# Main_Board.net
KiCad netlist of a schematic drawn in Altium Designer
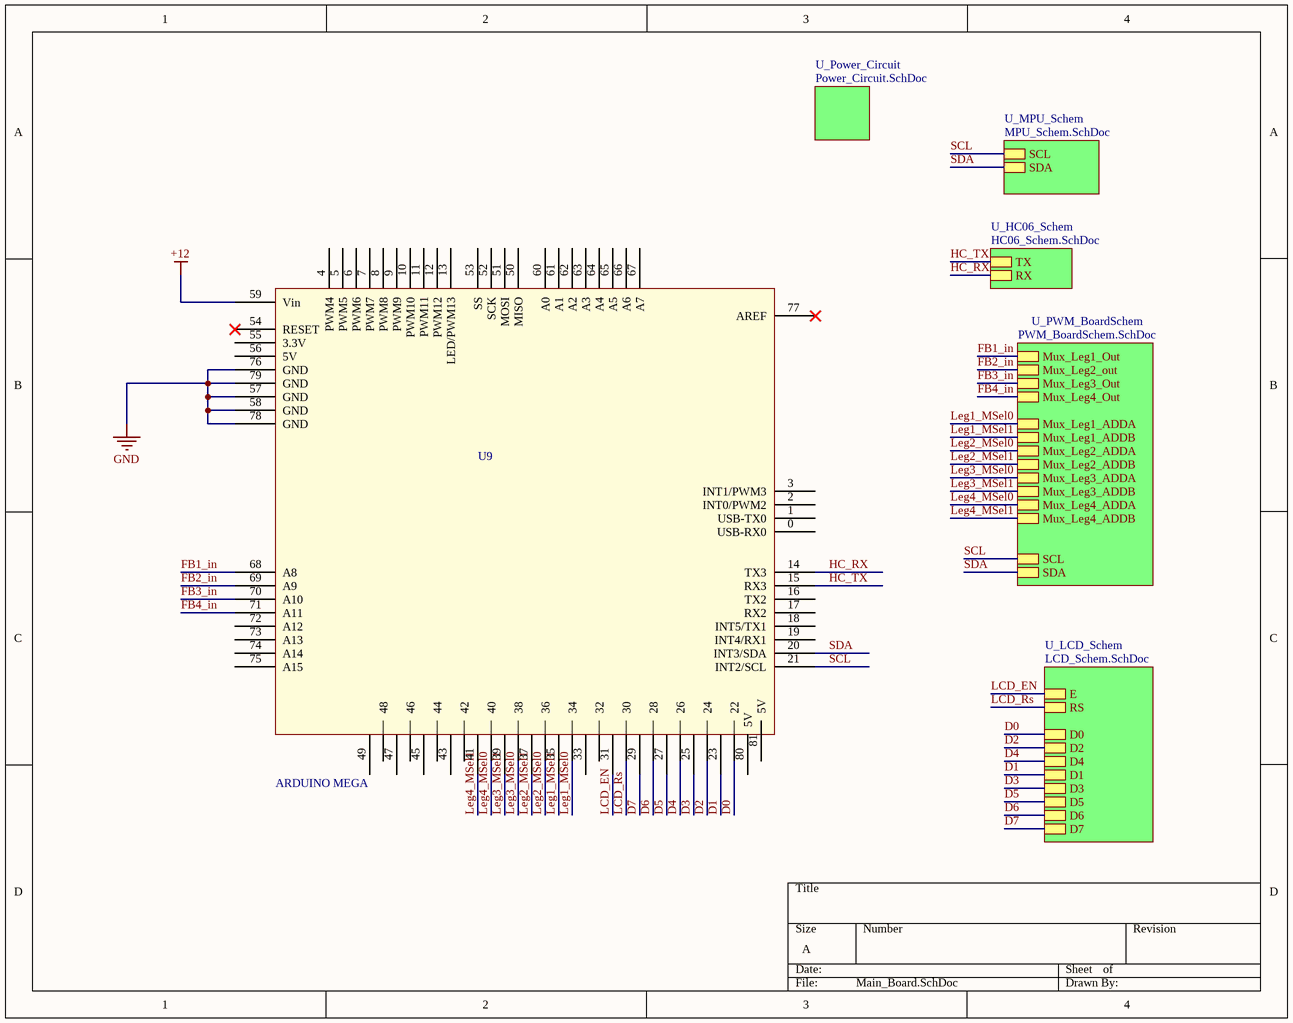
[diagram p0: Main_Board.SchDoc]

(export (version "E")
  (design (tool "Eeschema 10.0.6"))
  (components
    (comp (ref "U9")
      (value "ARDUINO MEGA")
      (footprint "ARDUINO MEGA")
      (libsource (lib "Arduino") (part "ARDUINO MEGA"))
    )
  )
  (nets
    (net (code "1") (name "+12") (class "Default")
      (node (ref "U9") (pin "59") (pinfunction "Vin_59") (pintype "passive"))
    )
    (net (code "2") (name "/D0") (class "Default")
      (node (ref "U9") (pin "22") (pinfunction "22_22") (pintype "passive"))
    )
    (net (code "3") (name "/D1") (class "Default")
      (node (ref "U9") (pin "23") (pinfunction "23_23") (pintype "passive"))
    )
    (net (code "4") (name "/D2") (class "Default")
      (node (ref "U9") (pin "24") (pinfunction "24_24") (pintype "passive"))
    )
    (net (code "5") (name "/D3") (class "Default")
      (node (ref "U9") (pin "25") (pinfunction "25_25") (pintype "passive"))
    )
    (net (code "6") (name "/D4") (class "Default")
      (node (ref "U9") (pin "26") (pinfunction "26_26") (pintype "passive"))
    )
    (net (code "7") (name "/D5") (class "Default")
      (node (ref "U9") (pin "27") (pinfunction "27_27") (pintype "passive"))
    )
    (net (code "8") (name "/D6") (class "Default")
      (node (ref "U9") (pin "28") (pinfunction "28_28") (pintype "passive"))
    )
    (net (code "9") (name "/D7") (class "Default")
      (node (ref "U9") (pin "29") (pinfunction "29_29") (pintype "passive"))
    )
    (net (code "10") (name "/FB1_in") (class "Default")
      (node (ref "U9") (pin "68") (pinfunction "A8_68") (pintype "passive"))
    )
    (net (code "11") (name "/FB2_in") (class "Default")
      (node (ref "U9") (pin "69") (pinfunction "A9_69") (pintype "passive"))
    )
    (net (code "12") (name "/FB3_in") (class "Default")
      (node (ref "U9") (pin "70") (pinfunction "A10_70") (pintype "passive"))
    )
    (net (code "13") (name "/FB4_in") (class "Default")
      (node (ref "U9") (pin "71") (pinfunction "A11_71") (pintype "passive"))
    )
    (net (code "14") (name "/HC_RX") (class "Default")
      (node (ref "U9") (pin "14") (pinfunction "TX3_14") (pintype "passive"))
    )
    (net (code "15") (name "/HC_TX") (class "Default")
      (node (ref "U9") (pin "15") (pinfunction "RX3_15") (pintype "passive"))
    )
    (net (code "16") (name "/LCD_EN") (class "Default")
      (node (ref "U9") (pin "31") (pinfunction "31_31") (pintype "passive"))
    )
    (net (code "17") (name "/LCD_Rs") (class "Default")
      (node (ref "U9") (pin "30") (pinfunction "30_30") (pintype "passive"))
    )
    (net (code "18") (name "/Leg1_MSel0") (class "Default")
      (node (ref "U9") (pin "34") (pinfunction "34_34") (pintype "passive"))
    )
    (net (code "19") (name "/Leg1_MSel1") (class "Default")
      (node (ref "U9") (pin "35") (pinfunction "35_35") (pintype "passive"))
    )
    (net (code "20") (name "/Leg2_MSel0") (class "Default")
      (node (ref "U9") (pin "36") (pinfunction "36_36") (pintype "passive"))
    )
    (net (code "21") (name "/Leg2_MSel1") (class "Default")
      (node (ref "U9") (pin "37") (pinfunction "37_37") (pintype "passive"))
    )
    (net (code "22") (name "/Leg3_MSel0") (class "Default")
      (node (ref "U9") (pin "38") (pinfunction "38_38") (pintype "passive"))
    )
    (net (code "23") (name "/Leg3_MSel1") (class "Default")
      (node (ref "U9") (pin "39") (pinfunction "39_39") (pintype "passive"))
    )
    (net (code "24") (name "/Leg4_MSel0") (class "Default")
      (node (ref "U9") (pin "40") (pinfunction "40_40") (pintype "passive"))
    )
    (net (code "25") (name "/Leg4_MSel1") (class "Default")
      (node (ref "U9") (pin "41") (pinfunction "41_41") (pintype "passive"))
    )
    (net (code "26") (name "/SCL") (class "Default")
      (node (ref "U9") (pin "21") (pinfunction "INT2/SCL_21") (pintype "passive"))
    )
    (net (code "27") (name "/SDA") (class "Default")
      (node (ref "U9") (pin "20") (pinfunction "INT3/SDA_20") (pintype "passive"))
    )
    (net (code "28") (name "GND") (class "Default")
      (node (ref "U9") (pin "57") (pinfunction "GND_57") (pintype "passive"))
      (node (ref "U9") (pin "58") (pinfunction "GND_58") (pintype "passive"))
      (node (ref "U9") (pin "76") (pinfunction "GND_76") (pintype "passive"))
      (node (ref "U9") (pin "78") (pinfunction "GND_78") (pintype "passive"))
      (node (ref "U9") (pin "79") (pinfunction "GND_79") (pintype "passive"))
    )
    (net (code "29") (name "unconnected-(U9-3.3V-Pad55)") (class "Default")
      (node (ref "U9") (pin "55") (pinfunction "3.3V_55") (pintype "passive"))
    )
    (net (code "30") (name "unconnected-(U9-5V-Pad56)") (class "Default")
      (node (ref "U9") (pin "56") (pinfunction "5V_56") (pintype "passive"))
    )
    (net (code "31") (name "unconnected-(U9-5V-Pad80)") (class "Default")
      (node (ref "U9") (pin "80") (pinfunction "5V_80") (pintype "passive"))
    )
    (net (code "32") (name "unconnected-(U9-5V-Pad81)") (class "Default")
      (node (ref "U9") (pin "81") (pinfunction "5V_81") (pintype "passive"))
    )
    (net (code "33") (name "unconnected-(U9-A0-Pad60)") (class "Default")
      (node (ref "U9") (pin "60") (pinfunction "A0_60") (pintype "passive"))
    )
    (net (code "34") (name "unconnected-(U9-A1-Pad61)") (class "Default")
      (node (ref "U9") (pin "61") (pinfunction "A1_61") (pintype "passive"))
    )
    (net (code "35") (name "unconnected-(U9-A2-Pad62)") (class "Default")
      (node (ref "U9") (pin "62") (pinfunction "A2_62") (pintype "passive"))
    )
    (net (code "36") (name "unconnected-(U9-A3-Pad63)") (class "Default")
      (node (ref "U9") (pin "63") (pinfunction "A3_63") (pintype "passive"))
    )
    (net (code "37") (name "unconnected-(U9-A4-Pad64)") (class "Default")
      (node (ref "U9") (pin "64") (pinfunction "A4_64") (pintype "passive"))
    )
    (net (code "38") (name "unconnected-(U9-A5-Pad65)") (class "Default")
      (node (ref "U9") (pin "65") (pinfunction "A5_65") (pintype "passive"))
    )
    (net (code "39") (name "unconnected-(U9-A6-Pad66)") (class "Default")
      (node (ref "U9") (pin "66") (pinfunction "A6_66") (pintype "passive"))
    )
    (net (code "40") (name "unconnected-(U9-A7-Pad67)") (class "Default")
      (node (ref "U9") (pin "67") (pinfunction "A7_67") (pintype "passive"))
    )
    (net (code "41") (name "unconnected-(U9-A12-Pad72)") (class "Default")
      (node (ref "U9") (pin "72") (pinfunction "A12_72") (pintype "passive"))
    )
    (net (code "42") (name "unconnected-(U9-A13-Pad73)") (class "Default")
      (node (ref "U9") (pin "73") (pinfunction "A13_73") (pintype "passive"))
    )
    (net (code "43") (name "unconnected-(U9-A14-Pad74)") (class "Default")
      (node (ref "U9") (pin "74") (pinfunction "A14_74") (pintype "passive"))
    )
    (net (code "44") (name "unconnected-(U9-A15-Pad75)") (class "Default")
      (node (ref "U9") (pin "75") (pinfunction "A15_75") (pintype "passive"))
    )
    (net (code "45") (name "unconnected-(U9-AREF-Pad77)") (class "Default")
      (node (ref "U9") (pin "77") (pinfunction "AREF_77") (pintype "passive+no_connect"))
    )
    (net (code "46") (name "unconnected-(U9-INT0{slash}PWM2-Pad2)") (class "Default")
      (node (ref "U9") (pin "2") (pinfunction "INT0/PWM2_2") (pintype "passive"))
    )
    (net (code "47") (name "unconnected-(U9-INT1{slash}PWM3-Pad3)") (class "Default")
      (node (ref "U9") (pin "3") (pinfunction "INT1/PWM3_3") (pintype "passive"))
    )
    (net (code "48") (name "unconnected-(U9-INT4{slash}RX1-Pad19)") (class "Default")
      (node (ref "U9") (pin "19") (pinfunction "INT4/RX1_19") (pintype "passive"))
    )
    (net (code "49") (name "unconnected-(U9-INT5{slash}TX1-Pad18)") (class "Default")
      (node (ref "U9") (pin "18") (pinfunction "INT5/TX1_18") (pintype "passive"))
    )
    (net (code "50") (name "unconnected-(U9-LED{slash}PWM13-Pad13)") (class "Default")
      (node (ref "U9") (pin "13") (pinfunction "LED/PWM13_13") (pintype "passive"))
    )
    (net (code "51") (name "unconnected-(U9-MISO-Pad50)") (class "Default")
      (node (ref "U9") (pin "50") (pinfunction "MISO_50") (pintype "passive"))
    )
    (net (code "52") (name "unconnected-(U9-MOSI-Pad51)") (class "Default")
      (node (ref "U9") (pin "51") (pinfunction "MOSI_51") (pintype "passive"))
    )
    (net (code "53") (name "unconnected-(U9-PWM4-Pad4)") (class "Default")
      (node (ref "U9") (pin "4") (pinfunction "PWM4_4") (pintype "passive"))
    )
    (net (code "54") (name "unconnected-(U9-PWM5-Pad5)") (class "Default")
      (node (ref "U9") (pin "5") (pinfunction "PWM5_5") (pintype "passive"))
    )
    (net (code "55") (name "unconnected-(U9-PWM6-Pad6)") (class "Default")
      (node (ref "U9") (pin "6") (pinfunction "PWM6_6") (pintype "passive"))
    )
    (net (code "56") (name "unconnected-(U9-PWM7-Pad7)") (class "Default")
      (node (ref "U9") (pin "7") (pinfunction "PWM7_7") (pintype "passive"))
    )
    (net (code "57") (name "unconnected-(U9-PWM8-Pad8)") (class "Default")
      (node (ref "U9") (pin "8") (pinfunction "PWM8_8") (pintype "passive"))
    )
    (net (code "58") (name "unconnected-(U9-PWM9-Pad9)") (class "Default")
      (node (ref "U9") (pin "9") (pinfunction "PWM9_9") (pintype "passive"))
    )
    (net (code "59") (name "unconnected-(U9-PWM10-Pad10)") (class "Default")
      (node (ref "U9") (pin "10") (pinfunction "PWM10_10") (pintype "passive"))
    )
    (net (code "60") (name "unconnected-(U9-PWM11-Pad11)") (class "Default")
      (node (ref "U9") (pin "11") (pinfunction "PWM11_11") (pintype "passive"))
    )
    (net (code "61") (name "unconnected-(U9-PWM12-Pad12)") (class "Default")
      (node (ref "U9") (pin "12") (pinfunction "PWM12_12") (pintype "passive"))
    )
    (net (code "62") (name "unconnected-(U9-Pad32)") (class "Default")
      (node (ref "U9") (pin "32") (pinfunction "32_32") (pintype "passive"))
    )
    (net (code "63") (name "unconnected-(U9-Pad33)") (class "Default")
      (node (ref "U9") (pin "33") (pinfunction "33_33") (pintype "passive"))
    )
    (net (code "64") (name "unconnected-(U9-Pad42)") (class "Default")
      (node (ref "U9") (pin "42") (pinfunction "42_42") (pintype "passive"))
    )
    (net (code "65") (name "unconnected-(U9-Pad43)") (class "Default")
      (node (ref "U9") (pin "43") (pinfunction "43_43") (pintype "passive"))
    )
    (net (code "66") (name "unconnected-(U9-Pad44)") (class "Default")
      (node (ref "U9") (pin "44") (pinfunction "44_44") (pintype "passive"))
    )
    (net (code "67") (name "unconnected-(U9-Pad45)") (class "Default")
      (node (ref "U9") (pin "45") (pinfunction "45_45") (pintype "passive"))
    )
    (net (code "68") (name "unconnected-(U9-Pad46)") (class "Default")
      (node (ref "U9") (pin "46") (pinfunction "46_46") (pintype "passive"))
    )
    (net (code "69") (name "unconnected-(U9-Pad47)") (class "Default")
      (node (ref "U9") (pin "47") (pinfunction "47_47") (pintype "passive"))
    )
    (net (code "70") (name "unconnected-(U9-Pad48)") (class "Default")
      (node (ref "U9") (pin "48") (pinfunction "48_48") (pintype "passive"))
    )
    (net (code "71") (name "unconnected-(U9-Pad49)") (class "Default")
      (node (ref "U9") (pin "49") (pinfunction "49_49") (pintype "passive"))
    )
    (net (code "72") (name "unconnected-(U9-RESET-Pad54)") (class "Default")
      (node (ref "U9") (pin "54") (pinfunction "RESET_54") (pintype "passive+no_connect"))
    )
    (net (code "73") (name "unconnected-(U9-RX2-Pad17)") (class "Default")
      (node (ref "U9") (pin "17") (pinfunction "RX2_17") (pintype "passive"))
    )
    (net (code "74") (name "unconnected-(U9-SCK-Pad52)") (class "Default")
      (node (ref "U9") (pin "52") (pinfunction "SCK_52") (pintype "passive"))
    )
    (net (code "75") (name "unconnected-(U9-SS-Pad53)") (class "Default")
      (node (ref "U9") (pin "53") (pinfunction "SS_53") (pintype "passive"))
    )
    (net (code "76") (name "unconnected-(U9-TX2-Pad16)") (class "Default")
      (node (ref "U9") (pin "16") (pinfunction "TX2_16") (pintype "passive"))
    )
    (net (code "77") (name "unconnected-(U9-USB-RX0-Pad0)") (class "Default")
      (node (ref "U9") (pin "0") (pinfunction "USB-RX0_0") (pintype "passive"))
    )
    (net (code "78") (name "unconnected-(U9-USB-TX0-Pad1)") (class "Default")
      (node (ref "U9") (pin "1") (pinfunction "USB-TX0_1") (pintype "passive"))
    )
  )
)
